# ConcentradorCUSB.net
KiCad netlist of a schematic drawn in EAGLE
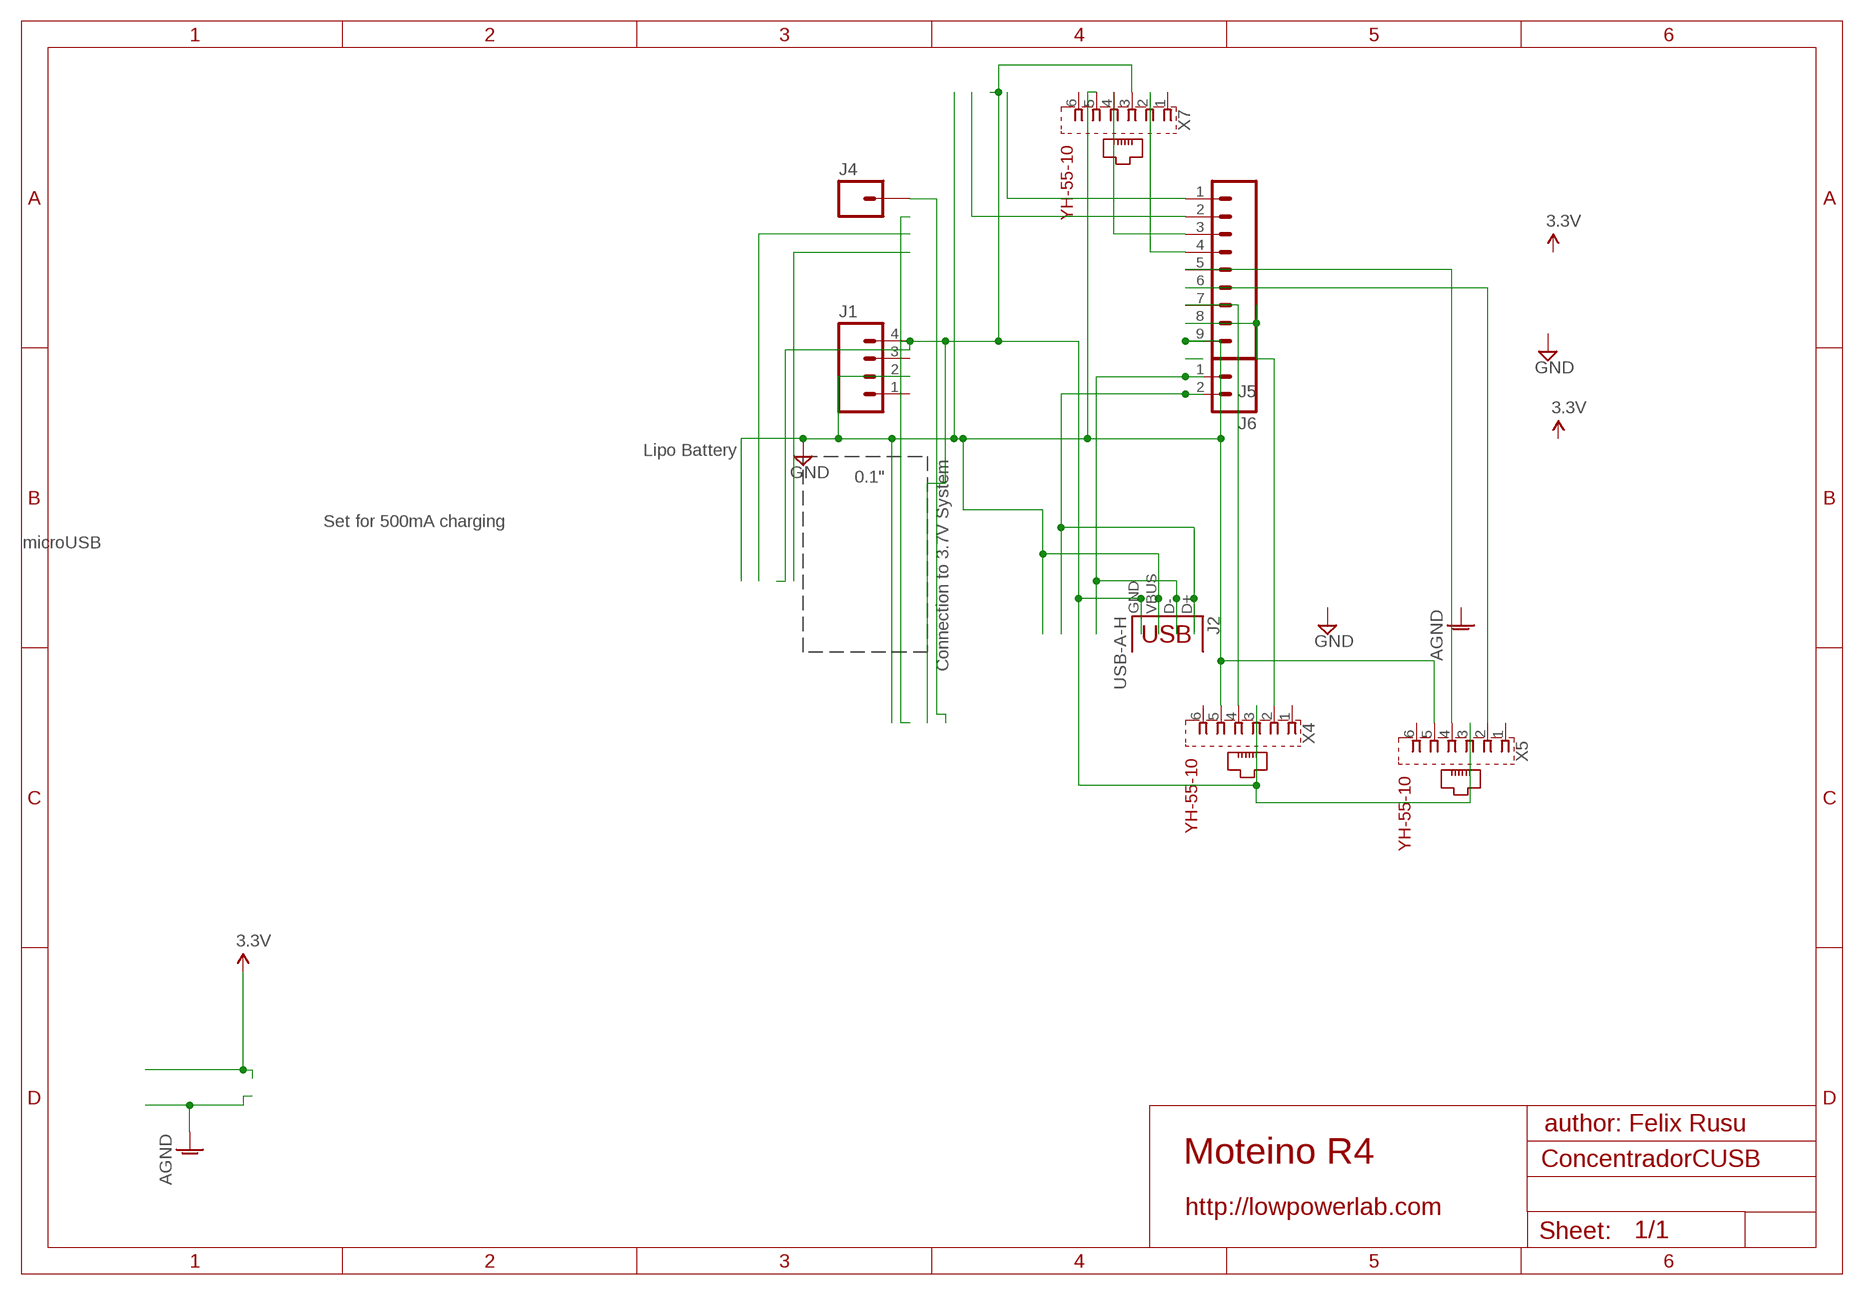
[diagram p0: schematic, sheet 1]

(export (version "E")
  (design (tool "Eeschema 10.0.6"))
  (components
    (comp (ref "J1")
      (value "M04PTH")
      (footprint "eagle-import:1X04")
      (libsource (lib "eagle-import") (part "M04PTH"))
    )
    (comp (ref "J2")
      (value "USB-A-H")
      (footprint "eagle-import:USB-A-H")
      (libsource (lib "eagle-import") (part "USB-A-H"))
    )
    (comp (ref "J4")
      (value "M01PTH")
      (footprint "eagle-import:1X01")
      (libsource (lib "eagle-import") (part "M01PTH"))
    )
    (comp (ref "J5")
      (value "M09")
      (footprint "eagle-import:1X09")
      (libsource (lib "eagle-import") (part "M09"))
    )
    (comp (ref "J6")
      (value "M02PTH")
      (footprint "eagle-import:1X02")
      (libsource (lib "eagle-import") (part "M02PTH"))
    )
    (comp (ref "X4")
      (value "YH-55-10")
      (footprint "eagle-import:YH-55-10")
      (libsource (lib "eagle-import") (part "YH-55-10"))
    )
    (comp (ref "X5")
      (value "YH-55-10")
      (footprint "eagle-import:YH-55-10")
      (libsource (lib "eagle-import") (part "YH-55-10"))
    )
    (comp (ref "X7")
      (value "YH-55-10")
      (footprint "eagle-import:YH-55-10")
      (libsource (lib "eagle-import") (part "YH-55-10"))
    )
  )
  (nets
    (net (code "3") (name "GND") (class "Default")
      (node (ref "J1") (pin "2") (pinfunction "2_2") (pintype "passive"))
      (node (ref "J2") (pin "VBUS") (pinfunction "VBUS_VBUS") (pintype "bidirectional"))
      (node (ref "J5") (pin "9") (pinfunction "9_9") (pintype "passive"))
      (node (ref "X4") (pin "5") (pinfunction "5_5") (pintype "passive"))
      (node (ref "X5") (pin "5") (pinfunction "5_5") (pintype "passive"))
      (node (ref "X7") (pin "5") (pinfunction "5_5") (pintype "passive"))
    )
    (net (code "4") (name "Net-(J1-Pad4)") (class "Default")
      (node (ref "J1") (pin "4") (pinfunction "4_4") (pintype "passive"))
      (node (ref "J2") (pin "GND") (pinfunction "GND_GND") (pintype "bidirectional"))
      (node (ref "X4") (pin "3") (pinfunction "3_3") (pintype "passive"))
      (node (ref "X5") (pin "3") (pinfunction "3_3") (pintype "passive"))
      (node (ref "X7") (pin "3") (pinfunction "3_3") (pintype "passive"))
    )
    (net (code "5") (name "Net-(J2-PadD+)") (class "Default")
      (node (ref "J2") (pin "D+") (pinfunction "D+_D+") (pintype "bidirectional"))
      (node (ref "J6") (pin "2") (pinfunction "2_2") (pintype "passive"))
    )
    (net (code "6") (name "Net-(J2-PadD-)") (class "Default")
      (node (ref "J2") (pin "D-") (pinfunction "D-_D-") (pintype "bidirectional"))
      (node (ref "J6") (pin "1") (pinfunction "1_1") (pintype "passive"))
    )
    (net (code "7") (name "Net-(J5-Pad3)") (class "Default")
      (node (ref "J5") (pin "3") (pinfunction "3_3") (pintype "passive"))
      (node (ref "X7") (pin "4") (pinfunction "4_4") (pintype "passive"))
    )
    (net (code "8") (name "Net-(J5-Pad4)") (class "Default")
      (node (ref "J5") (pin "4") (pinfunction "4_4") (pintype "passive"))
      (node (ref "X7") (pin "2") (pinfunction "2_2") (pintype "passive"))
    )
    (net (code "9") (name "Net-(J5-Pad5)") (class "Default")
      (node (ref "J5") (pin "5") (pinfunction "5_5") (pintype "passive"))
      (node (ref "X5") (pin "4") (pinfunction "4_4") (pintype "passive"))
    )
    (net (code "10") (name "Net-(J5-Pad6)") (class "Default")
      (node (ref "J5") (pin "6") (pinfunction "6_6") (pintype "passive"))
      (node (ref "X5") (pin "2") (pinfunction "2_2") (pintype "passive"))
    )
    (net (code "11") (name "Net-(J5-Pad7)") (class "Default")
      (node (ref "J5") (pin "7") (pinfunction "7_7") (pintype "passive"))
      (node (ref "X4") (pin "4") (pinfunction "4_4") (pintype "passive"))
    )
    (net (code "12") (name "Net-(J5-Pad8)") (class "Default")
      (node (ref "J5") (pin "8") (pinfunction "8_8") (pintype "passive"))
      (node (ref "X4") (pin "2") (pinfunction "2_2") (pintype "passive"))
    )
    (net (code "13") (name "unconnected-(J1-Pad1)") (class "Default")
      (node (ref "J1") (pin "1") (pinfunction "1_1") (pintype "passive"))
    )
    (net (code "14") (name "unconnected-(J1-Pad3)") (class "Default")
      (node (ref "J1") (pin "3") (pinfunction "3_3") (pintype "passive"))
    )
    (net (code "15") (name "unconnected-(J4-Pad1)") (class "Default")
      (node (ref "J4") (pin "1") (pinfunction "1_1") (pintype "passive"))
    )
    (net (code "16") (name "unconnected-(J5-Pad1)") (class "Default")
      (node (ref "J5") (pin "1") (pinfunction "1_1") (pintype "passive"))
    )
    (net (code "17") (name "unconnected-(J5-Pad2)") (class "Default")
      (node (ref "J5") (pin "2") (pinfunction "2_2") (pintype "passive"))
    )
    (net (code "18") (name "unconnected-(X4-Pad1)") (class "Default")
      (node (ref "X4") (pin "1") (pinfunction "1_1") (pintype "passive"))
    )
    (net (code "19") (name "unconnected-(X4-Pad6)") (class "Default")
      (node (ref "X4") (pin "6") (pinfunction "6_6") (pintype "passive"))
    )
    (net (code "20") (name "unconnected-(X5-Pad1)") (class "Default")
      (node (ref "X5") (pin "1") (pinfunction "1_1") (pintype "passive"))
    )
    (net (code "21") (name "unconnected-(X5-Pad6)") (class "Default")
      (node (ref "X5") (pin "6") (pinfunction "6_6") (pintype "passive"))
    )
    (net (code "22") (name "unconnected-(X7-Pad1)") (class "Default")
      (node (ref "X7") (pin "1") (pinfunction "1_1") (pintype "passive"))
    )
    (net (code "23") (name "unconnected-(X7-Pad6)") (class "Default")
      (node (ref "X7") (pin "6") (pinfunction "6_6") (pintype "passive"))
    )
  )
)
